# RdriveC1.net
KiCad netlist of a schematic drawn in Altium Designer
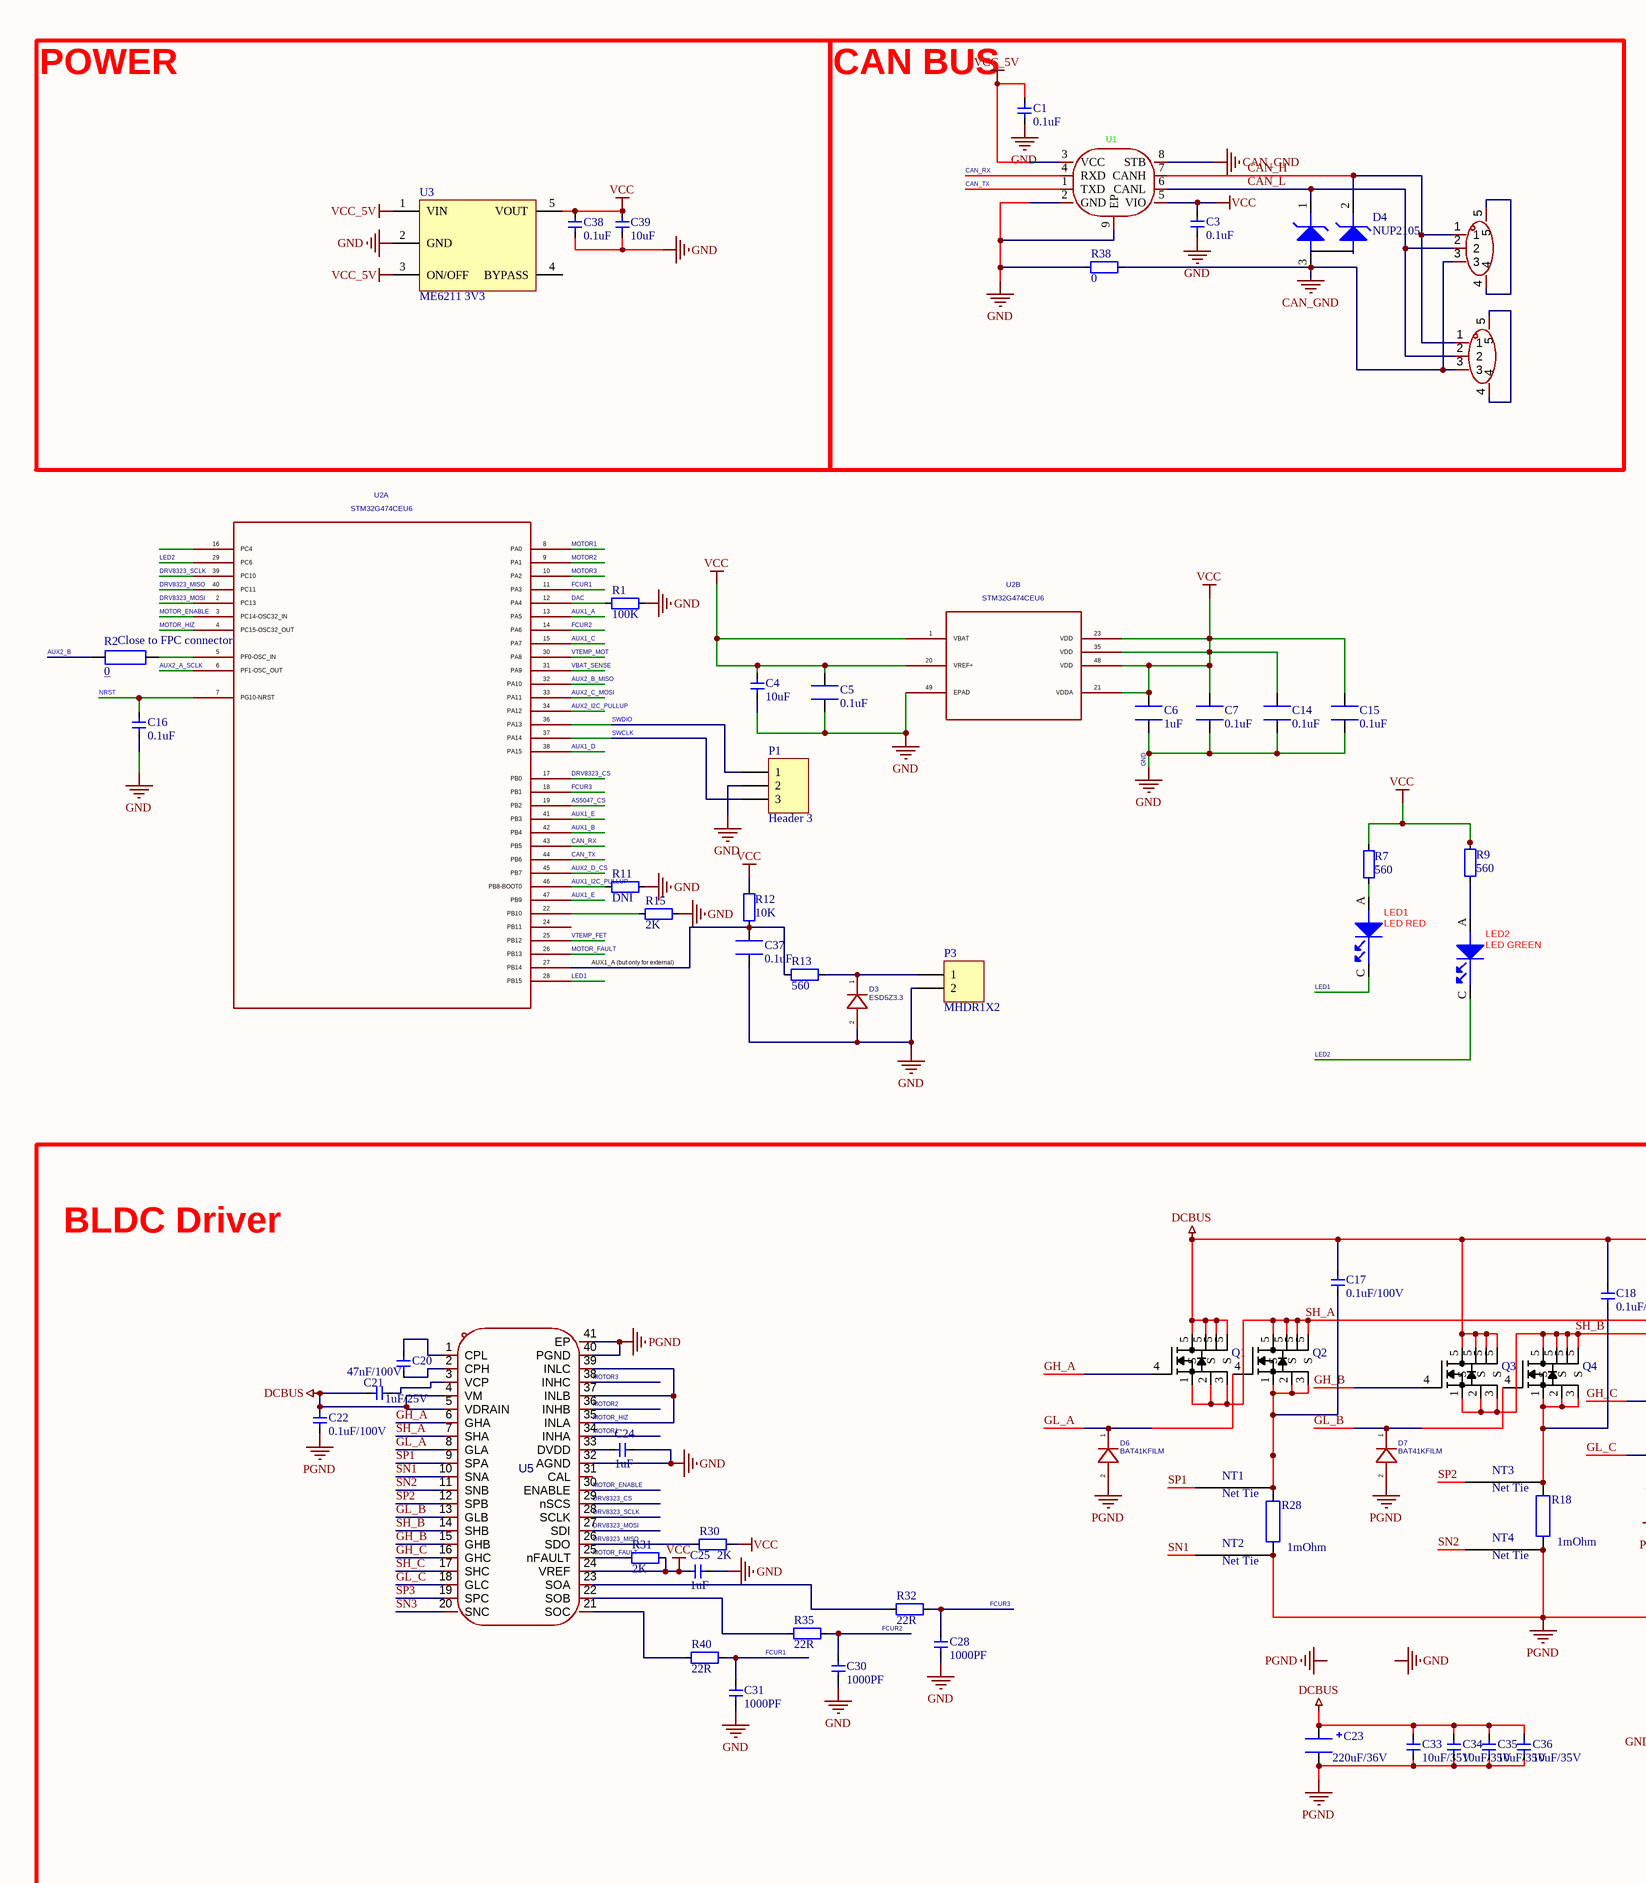
[diagram p0: RdriveC1.SchDoc, left]
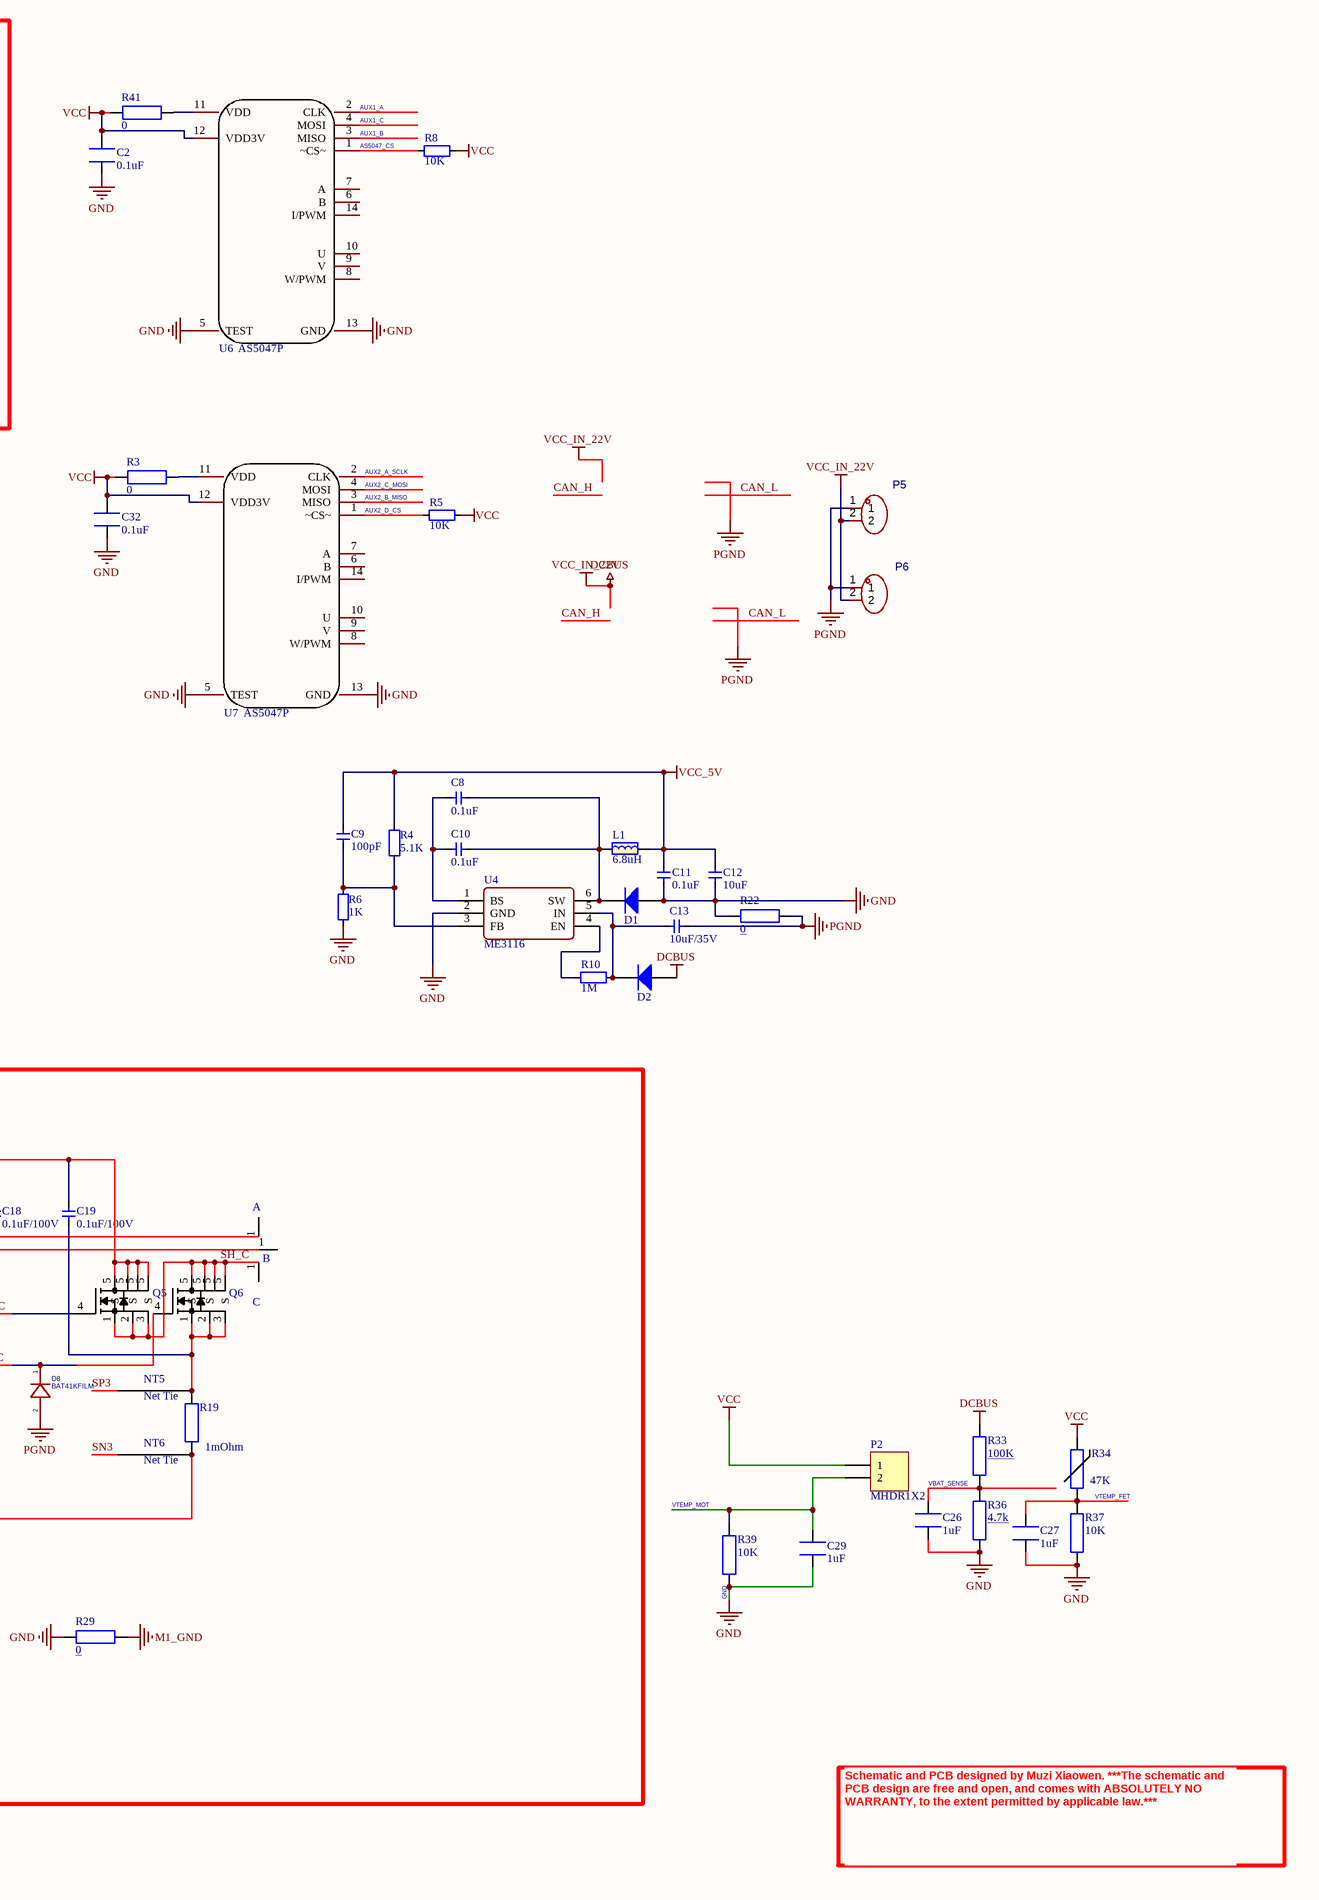
[diagram p1: RdriveC1.SchDoc, right]

(export (version "E")
  (design (tool "Eeschema 10.0.6"))
  (components
    (comp (ref "A") (value "M") (footprint "motor") (libsource (lib "RdriveS1") (part "M")))
    (comp (ref "B") (value "M") (footprint "motor") (libsource (lib "RdriveS1") (part "M")))
    (comp (ref "C") (value "M") (footprint "motor") (libsource (lib "RdriveS1") (part "M")))
    (comp (ref "C1")
      (value "0.1uF")
      (footprint "CAP_0402")
      (description "Capacitor")
      (libsource (lib "MyPcbLib") (part "电容-0402"))
    )
    (comp (ref "C2")
      (value "0.1uF")
      (footprint "CAP_0402")
      (description "CAP CER 0.1UF 50V X7R 0603")
      (fields
        (field (name "MANUFACTURER") "Murata Electronics North America")
        (field (name "MANUFACTURER PART NUMBER") "GRM188R71H104KA93D")
      )
      (libsource (lib "CustomComponents") (part "GRM188R71H104KA93D"))
    )
    (comp (ref "C3")
      (value "0.1uF")
      (footprint "CAP_0402")
      (description "Capacitor")
      (libsource (lib "MyPcbLib") (part "电容-0402"))
    )
    (comp (ref "C4")
      (value "10uF")
      (footprint "CAP_0402")
      (description "Capacitor")
      (libsource (lib "MyPcbLib") (part "电容-0402"))
    )
    (comp (ref "C5")
      (value "0.1uF")
      (footprint "CAP_0402")
      (description "CAP CER 0.1UF 50V X7R 0603")
      (fields
        (field (name "MANUFACTURER") "Murata Electronics North America")
        (field (name "MANUFACTURER PART NUMBER") "GRM188R71H104KA93D")
      )
      (libsource (lib "CustomComponents") (part "GRM188R71H104KA93D"))
    )
    (comp (ref "C6")
      (value "1uF")
      (footprint "CAP_0402")
      (description "CAP CER 1UF 50V X7R 0603")
      (fields
        (field (name "MANUFACTURER") "Murata Electronics North America")
        (field (name "MANUFACTURER PART NUMBER") "GRM188R71H104KA93D")
      )
      (libsource (lib "CustomComponents") (part "GRM188R71H104KA93D"))
    )
    (comp (ref "C7")
      (value "0.1uF")
      (footprint "CAP_0402")
      (description "CAP CER 0.1UF 50V X7R 0603")
      (fields
        (field (name "MANUFACTURER") "Murata Electronics North America")
        (field (name "MANUFACTURER PART NUMBER") "GRM188R71H104KA93D")
      )
      (libsource (lib "CustomComponents") (part "GRM188R71H104KA93D"))
    )
    (comp (ref "C8")
      (value "0.1uF")
      (footprint "CAP_0402")
      (description "Capacitor")
      (libsource (lib "MyPcbLib") (part "电容-0402"))
    )
    (comp (ref "C9")
      (value "100pF")
      (footprint "CAP_0402")
      (description "Capacitor")
      (libsource (lib "MyPcbLib") (part "电容-0402"))
    )
    (comp (ref "C10")
      (value "0.1uF")
      (footprint "CAP_0402")
      (description "Capacitor")
      (libsource (lib "MyPcbLib") (part "电容-0402"))
    )
    (comp (ref "C11")
      (value "0.1uF")
      (footprint "CAP_0402")
      (description "Capacitor")
      (libsource (lib "MyPcbLib") (part "电容-0402"))
    )
    (comp (ref "C12")
      (value "10uF")
      (footprint "CAP_0402")
      (description "Capacitor")
      (libsource (lib "MyPcbLib") (part "电容-0402"))
    )
    (comp (ref "C13")
      (value "10uF/35V")
      (footprint "C0603")
      (description "Capacitor")
      (libsource (lib "MyPcbLib") (part "电容-0402"))
    )
    (comp (ref "C14")
      (value "0.1uF")
      (footprint "CAP_0402")
      (description "CAP CER 0.1UF 50V X7R 0603")
      (fields
        (field (name "MANUFACTURER") "Murata Electronics North America")
        (field (name "MANUFACTURER PART NUMBER") "GRM188R71H104KA93D")
      )
      (libsource (lib "CustomComponents") (part "GRM188R71H104KA93D"))
    )
    (comp (ref "C15")
      (value "0.1uF")
      (footprint "CAP_0402")
      (description "CAP CER 0.1UF 50V X7R 0603")
      (fields
        (field (name "MANUFACTURER") "Murata Electronics North America")
        (field (name "MANUFACTURER PART NUMBER") "GRM188R71H104KA93D")
      )
      (libsource (lib "CustomComponents") (part "GRM188R71H104KA93D"))
    )
    (comp (ref "C16")
      (value "0.1uF")
      (footprint "CAP_0402")
      (description "Capacitor")
      (libsource (lib "MyPcbLib") (part "电容-0402"))
    )
    (comp (ref "C17")
      (value "0.1uF/100V")
      (footprint "1206-RES")
      (description "Capacitor")
      (libsource (lib "MyPcbLib") (part "电容-0402"))
    )
    (comp (ref "C18")
      (value "0.1uF/100V")
      (footprint "1206-RES")
      (description "Capacitor")
      (libsource (lib "MyPcbLib") (part "电容-0402"))
    )
    (comp (ref "C19")
      (value "0.1uF/100V")
      (footprint "1206-RES")
      (description "Capacitor")
      (libsource (lib "MyPcbLib") (part "电容-0402"))
    )
    (comp (ref "C20")
      (value "47nF/100V")
      (footprint "C0603")
      (description "Capacitor")
      (libsource (lib "MyPcbLib") (part "电容-0402"))
    )
    (comp (ref "C21")
      (value "1uF/25V")
      (footprint "C0603")
      (description "Capacitor")
      (libsource (lib "MyPcbLib") (part "电容-0402"))
    )
    (comp (ref "C22")
      (value "0.1uF/100V")
      (footprint "C0603")
      (description "Capacitor")
      (libsource (lib "MyPcbLib") (part "电容-0402"))
    )
    (comp (ref "C23")
      (value "220uF/36V")
      (footprint "3d-CAP-SMD_BD6.3-L6.6-W6.6-LS7.2-FD")
      (description "CAP, FP Series, 470 µF, 25 V, Radial Can - SMD, 10 mm")
      (fields
        (field (name "MANUFACTURER") "Panasonic Electronic Components")
        (field (name "TOLERANCE") "±20%")
      )
      (libsource (lib "CustomComponents") (part "EEEFP1E471AP"))
    )
    (comp (ref "C24")
      (value "1uF")
      (footprint "CAP_0402")
      (description "Capacitor")
      (libsource (lib "MyPcbLib") (part "电容-0402"))
    )
    (comp (ref "C25")
      (value "1uF")
      (footprint "CAP_0402")
      (description "Capacitor")
      (libsource (lib "MyPcbLib") (part "电容-0402"))
    )
    (comp (ref "C26")
      (value "1uF")
      (footprint "CAP_0402")
      (description "CAP CER 1UF 50V X7R 0603")
      (fields
        (field (name "MANUFACTURER") "Murata Electronics North America")
        (field (name "MANUFACTURER PART NUMBER") "GRM188R71H104KA93D")
      )
      (libsource (lib "CustomComponents") (part "GRM188R71H104KA93D"))
    )
    (comp (ref "C27")
      (value "1uF")
      (footprint "CAP_0402")
      (description "CAP CER 1UF 50V X7R 0603")
      (fields
        (field (name "MANUFACTURER") "Murata Electronics North America")
        (field (name "MANUFACTURER PART NUMBER") "GRM188R71H104KA93D")
      )
      (libsource (lib "CustomComponents") (part "GRM188R71H104KA93D"))
    )
    (comp (ref "C28")
      (value "1000PF")
      (footprint "CAP_0402")
      (description "Capacitor")
      (libsource (lib "MyPcbLib") (part "电容-0402"))
    )
    (comp (ref "C29")
      (value "1uF")
      (footprint "CAP_0402")
      (description "CAP CER 1UF 50V X7R 0603")
      (fields
        (field (name "MANUFACTURER") "Murata Electronics North America")
        (field (name "MANUFACTURER PART NUMBER") "GRM188R71H104KA93D")
      )
      (libsource (lib "CustomComponents") (part "GRM188R71H104KA93D"))
    )
    (comp (ref "C30")
      (value "1000PF")
      (footprint "CAP_0402")
      (description "Capacitor")
      (libsource (lib "MyPcbLib") (part "电容-0402"))
    )
    (comp (ref "C31")
      (value "1000PF")
      (footprint "CAP_0402")
      (description "Capacitor")
      (libsource (lib "MyPcbLib") (part "电容-0402"))
    )
    (comp (ref "C32")
      (value "0.1uF")
      (footprint "CAP_0402")
      (description "CAP CER 0.1UF 50V X7R 0603")
      (fields
        (field (name "MANUFACTURER") "Murata Electronics North America")
        (field (name "MANUFACTURER PART NUMBER") "GRM188R71H104KA93D")
      )
      (libsource (lib "CustomComponents") (part "GRM188R71H104KA93D"))
    )
    (comp (ref "C33")
      (value "10uF/35V")
      (footprint "C0603-3d")
      (description "Capacitor")
      (libsource (lib "MyPcbLib") (part "电容-0402"))
    )
    (comp (ref "C34")
      (value "10uF/35V")
      (footprint "C0603-3d")
      (description "Capacitor")
      (libsource (lib "MyPcbLib") (part "电容-0402"))
    )
    (comp (ref "C35")
      (value "10uF/35V")
      (footprint "C0603-3d")
      (description "Capacitor")
      (libsource (lib "MyPcbLib") (part "电容-0402"))
    )
    (comp (ref "C36")
      (value "10uF/35V")
      (footprint "C0603-3d")
      (description "Capacitor")
      (libsource (lib "MyPcbLib") (part "电容-0402"))
    )
    (comp (ref "C37")
      (value "0.1uF")
      (footprint "CAP_0402")
      (description "CAP CER 0.1UF 50V X7R 0603")
      (fields
        (field (name "MANUFACTURER") "Murata Electronics North America")
        (field (name "MANUFACTURER PART NUMBER") "GRM188R71H104KA93D")
      )
      (libsource (lib "CustomComponents") (part "GRM188R71H104KA93D"))
    )
    (comp (ref "C38")
      (value "0.1uF")
      (footprint "CAP_0402")
      (description "Capacitor")
      (libsource (lib "MyPcbLib") (part "电容-0402"))
    )
    (comp (ref "C39")
      (value "10uF")
      (footprint "CAP_0402")
      (description "Capacitor")
      (libsource (lib "MyPcbLib") (part "电容-0402"))
    )
    (comp (ref "CN1")
      (value "WAFER-GH1.25-3PLT-W1-P")
      (footprint "CONN-SMD_WAFER-GH1.25-3PLT-W1-P")
      (libsource (lib "altium-import") (part "root_0_WAFER-GH1.25-3PLT-W1-P_"))
    )
    (comp (ref "CN2")
      (value "WAFER-GH1.25-3PLT-W1-P")
      (footprint "CONN-SMD_WAFER-GH1.25-3PLT-W1-P")
      (libsource (lib "altium-import") (part "root_0_WAFER-GH1.25-3PLT-W1-P_"))
    )
    (comp (ref "D1")
      (value "二极管-5819W")
      (footprint "SOD-323")
      (description "40V")
      (libsource (lib "MyPcbLib") (part "二极管-5819W"))
    )
    (comp (ref "D2")
      (value "二极管-5819W")
      (footprint "SOD-323")
      (description "40V")
      (libsource (lib "MyPcbLib") (part "二极管-5819W"))
    )
    (comp (ref "D3")
      (value "ESD5Z3.3")
      (footprint "moteus:SOD-523_STM")
      (fields
        (field (name "MPN") "BAT41KFILM")
        (field (name "MF") "ST")
        (field (name "Comment") "moteus_BAT41KFILM")
      )
      (libsource (lib "altium-import") (part "root_1_moteus_BAT41KFILM_"))
    )
    (comp (ref "D4") (value "NUP2105") (footprint "SOT23-3") (libsource (lib "Schlib1") (part "NUP2105")))
    (comp (ref "D6")
      (value "BAT41KFILM")
      (footprint "moteus:SOD-523_STM")
      (fields (field (name "MF") "ST") (field (name "Comment") "moteus_BAT41KFILM"))
      (libsource (lib "altium-import") (part "root_1_moteus_BAT41KFILM_"))
    )
    (comp (ref "D7")
      (value "BAT41KFILM")
      (footprint "moteus:SOD-523_STM")
      (fields (field (name "MF") "ST") (field (name "Comment") "moteus_BAT41KFILM"))
      (libsource (lib "altium-import") (part "root_1_moteus_BAT41KFILM_"))
    )
    (comp (ref "D8")
      (value "BAT41KFILM")
      (footprint "moteus:SOD-523_STM")
      (fields (field (name "MF") "ST") (field (name "Comment") "moteus_BAT41KFILM"))
      (libsource (lib "altium-import") (part "root_1_moteus_BAT41KFILM_"))
    )
    (comp (ref "L1") (value "6.8uH") (footprint "IND-201612") (libsource (lib "MyPcbLib") (part "电感-201612")))
    (comp (ref "LED1")
      (value "LED RED")
      (description "LED GRN SGL RA 25mA 4.1V SMD")
      (libsource (lib "*") (part "LED"))
    )
    (comp (ref "LED2")
      (value "LED GREEN")
      (description "LED GRN SGL RA 25mA 4.1V SMD")
      (libsource (lib "*") (part "LED"))
    )
    (comp (ref "NT1")
      (value "0.25mm")
      (footprint "NetTie_0.25mm")
      (libsource (lib "CustomComponents") (part "NetTie_0.25mm"))
    )
    (comp (ref "NT2")
      (value "0.25mm")
      (footprint "NetTie_0.25mm")
      (libsource (lib "CustomComponents") (part "NetTie_0.25mm"))
    )
    (comp (ref "NT3")
      (value "0.25mm")
      (footprint "NetTie_0.25mm")
      (libsource (lib "CustomComponents") (part "NetTie_0.25mm"))
    )
    (comp (ref "NT4")
      (value "0.25mm")
      (footprint "NetTie_0.25mm")
      (libsource (lib "CustomComponents") (part "NetTie_0.25mm"))
    )
    (comp (ref "NT5")
      (value "0.25mm")
      (footprint "NetTie_0.25mm")
      (libsource (lib "CustomComponents") (part "NetTie_0.25mm"))
    )
    (comp (ref "NT6")
      (value "0.25mm")
      (footprint "NetTie_0.25mm")
      (libsource (lib "CustomComponents") (part "NetTie_0.25mm"))
    )
    (comp (ref "P1")
      (value "Header 3")
      (footprint "HDR1X3")
      (description "Header, 3-Pin")
      (fields (field (name "PUBLISHER") "Altium Limited"))
      (libsource (lib "Miscellaneous Connectors") (part "Header 3"))
    )
    (comp (ref "P2")
      (value "MHDR1X2")
      (footprint "MHDR1X2")
      (description "Header, 2-Pin")
      (fields (field (name "PUBLISHER") "Altium Limited"))
      (libsource (lib "Miscellaneous Connectors") (part "MHDR1X2"))
    )
    (comp (ref "P3")
      (value "MHDR1X2")
      (footprint "CONN-TH_2P-P1.50_HCTL_HC-ZH1.5-2AW")
      (description "Header, 2-Pin")
      (fields (field (name "PUBLISHER") "Altium Limited"))
      (libsource (lib "Miscellaneous Connectors") (part "MHDR1X2"))
    )
    (comp (ref "P5")
      (value "HC-MX3.0-2*1AW")
      (footprint "CONN-TH_XT30UW-F.G.Y")
      (libsource (lib "altium-import") (part "root_0_HC-MX3.0-2*1AW_"))
    )
    (comp (ref "P6")
      (value "HC-MX3.0-2*1AW")
      (footprint "CONN-TH_XT30UW-F.G.Y")
      (libsource (lib "altium-import") (part "root_0_HC-MX3.0-2*1AW_"))
    )
    (comp (ref "Q1")
      (value "SE3082G2")
      (footprint "DFN-8_L5.9-W5.2-P1.27-LS6.2-BL")
      (description "MOSFET N-CH 30V 13A SO8FL")
      (fields
        (field (name "MANUFACTURER") "ON Semiconductor")
        (field (name "MANUFACTURER PART NUMBER") "NTMFS4935NT1G")
      )
      (libsource (lib "odrivelib") (part "SE3082G2"))
    )
    (comp (ref "Q2")
      (value "SE3082G2")
      (footprint "DFN-8_L5.9-W5.2-P1.27-LS6.2-BL")
      (description "MOSFET N-CH 30V 13A SO8FL")
      (fields
        (field (name "MANUFACTURER") "ON Semiconductor")
        (field (name "MANUFACTURER PART NUMBER") "NTMFS4935NT1G")
      )
      (libsource (lib "odrivelib") (part "SE3082G2"))
    )
    (comp (ref "Q3")
      (value "SE3082G2")
      (footprint "DFN-8_L5.9-W5.2-P1.27-LS6.2-BL")
      (description "MOSFET N-CH 30V 13A SO8FL")
      (fields
        (field (name "MANUFACTURER") "ON Semiconductor")
        (field (name "MANUFACTURER PART NUMBER") "NTMFS4935NT1G")
      )
      (libsource (lib "odrivelib") (part "SE3082G2"))
    )
    (comp (ref "Q4")
      (value "SE3082G2")
      (footprint "DFN-8_L5.9-W5.2-P1.27-LS6.2-BL")
      (description "MOSFET N-CH 30V 13A SO8FL")
      (fields
        (field (name "MANUFACTURER") "ON Semiconductor")
        (field (name "MANUFACTURER PART NUMBER") "NTMFS4935NT1G")
      )
      (libsource (lib "odrivelib") (part "SE3082G2"))
    )
    (comp (ref "Q5")
      (value "SE3082G2")
      (footprint "DFN-8_L5.9-W5.2-P1.27-LS6.2-BL")
      (description "MOSFET N-CH 30V 13A SO8FL")
      (fields
        (field (name "MANUFACTURER") "ON Semiconductor")
        (field (name "MANUFACTURER PART NUMBER") "NTMFS4935NT1G")
      )
      (libsource (lib "odrivelib") (part "SE3082G2"))
    )
    (comp (ref "Q6")
      (value "SE3082G2")
      (footprint "DFN-8_L5.9-W5.2-P1.27-LS6.2-BL")
      (description "MOSFET N-CH 30V 13A SO8FL")
      (fields
        (field (name "MANUFACTURER") "ON Semiconductor")
        (field (name "MANUFACTURER PART NUMBER") "NTMFS4935NT1G")
      )
      (libsource (lib "odrivelib") (part "SE3082G2"))
    )
    (comp (ref "R1")
      (value "100K")
      (footprint "RES_0402")
      (description "Resistor")
      (libsource (lib "MyPcbLib") (part "电阻-0402"))
    )
    (comp (ref "R2")
      (value "0")
      (footprint "RES_0402")
      (description "RES SMD 1K OHM 1% 1/10W 0603")
      (fields (field (name "MANUFACTURER") "Yageo") (field (name "TOLERANCE") "±1%"))
      (libsource (lib "CustomComponents") (part "RC0603FR-071KL"))
    )
    (comp (ref "R3")
      (value "0")
      (footprint "RES_0402")
      (description "RES SMD 1K OHM 1% 1/10W 0603")
      (fields (field (name "MANUFACTURER") "Yageo") (field (name "TOLERANCE") "±1%"))
      (libsource (lib "CustomComponents") (part "RC0603FR-071KL"))
    )
    (comp (ref "R4")
      (value "5.1K")
      (footprint "RES_0402")
      (description "Resistor")
      (libsource (lib "") (part "电阻-0402_1"))
    )
    (comp (ref "R5")
      (value "10K")
      (footprint "RES_0402")
      (description "Resistor")
      (libsource (lib "") (part "电阻-0402_2"))
    )
    (comp (ref "R6")
      (value "1K")
      (footprint "RES_0402")
      (description "Resistor")
      (libsource (lib "") (part "电阻-0402_1"))
    )
    (comp (ref "R7")
      (value "560")
      (footprint "RES_0402")
      (description "Resistor")
      (libsource (lib "") (part "电阻-0402_1"))
    )
    (comp (ref "R8")
      (value "10K")
      (footprint "RES_0402")
      (description "Resistor")
      (libsource (lib "") (part "电阻-0402_2"))
    )
    (comp (ref "R9")
      (value "560")
      (footprint "RES_0402")
      (description "Resistor")
      (libsource (lib "") (part "电阻-0402_1"))
    )
    (comp (ref "R10")
      (value "1M")
      (footprint "RES_0402")
      (description "Resistor")
      (libsource (lib "MyPcbLib") (part "电阻-0402"))
    )
    (comp (ref "R11")
      (value "DNI")
      (footprint "RES_0402")
      (description "Resistor")
      (libsource (lib "MyPcbLib") (part "电阻-0402"))
    )
    (comp (ref "R12")
      (value "10K")
      (footprint "RES_0402")
      (description "Resistor")
      (libsource (lib "") (part "电阻-0402_1"))
    )
    (comp (ref "R13")
      (value "560")
      (footprint "RES_0402")
      (description "Resistor")
      (libsource (lib "MyPcbLib") (part "电阻-0402"))
    )
    (comp (ref "R15")
      (value "2K")
      (footprint "RES_0402")
      (description "Resistor")
      (libsource (lib "MyPcbLib") (part "电阻-0402"))
    )
    (comp (ref "R18")
      (value "1mOhm")
      (footprint "1206-RES")
      (description "RES SMD 0.0005 OHM 1% 3W 2512")
      (fields (field (name "MANUFACTURER") "Riedon") (field (name "TOLERANCE") "±1%"))
      (libsource (lib "CustomComponents") (part "CSR2512C0R0005F"))
    )
    (comp (ref "R19")
      (value "1mOhm")
      (footprint "1206-RES")
      (description "RES SMD 0.0005 OHM 1% 3W 2512")
      (fields (field (name "MANUFACTURER") "Riedon") (field (name "TOLERANCE") "±1%"))
      (libsource (lib "CustomComponents") (part "CSR2512C0R0005F"))
    )
    (comp (ref "R22")
      (value "0")
      (footprint "1206-RES")
      (description "RES SMD 1K OHM 1% 1/10W 0603")
      (fields (field (name "MANUFACTURER") "Yageo") (field (name "TOLERANCE") "±1%"))
      (libsource (lib "CustomComponents") (part "RC0603FR-071KL"))
    )
    (comp (ref "R28")
      (value "1mOhm")
      (footprint "1206-RES")
      (description "RES SMD 0.0005 OHM 1% 3W 2512")
      (fields (field (name "MANUFACTURER") "Riedon") (field (name "TOLERANCE") "±1%"))
      (libsource (lib "CustomComponents") (part "CSR2512C0R0005F"))
    )
    (comp (ref "R29")
      (value "0")
      (footprint "RES_0402")
      (description "RES SMD 1K OHM 1% 1/10W 0603")
      (fields (field (name "MANUFACTURER") "Yageo") (field (name "TOLERANCE") "±1%"))
      (libsource (lib "CustomComponents") (part "RC0603FR-071KL"))
    )
    (comp (ref "R30")
      (value "2K")
      (footprint "RES_0402")
      (description "Resistor")
      (libsource (lib "MyPcbLib") (part "电阻-0402"))
    )
    (comp (ref "R31")
      (value "2K")
      (footprint "RES_0402")
      (description "Resistor")
      (libsource (lib "MyPcbLib") (part "电阻-0402"))
    )
    (comp (ref "R32")
      (value "22R")
      (footprint "RES_0402")
      (description "Resistor")
      (libsource (lib "") (part "电阻-0402_2"))
    )
    (comp (ref "R33")
      (value "100K")
      (footprint "RES_0402")
      (description "RES SMD 1K OHM 1% 1/10W 0603")
      (fields (field (name "MANUFACTURER") "Yageo") (field (name "TOLERANCE") "±1%"))
      (libsource (lib "CustomComponents") (part "RC0603FR-071KL"))
    )
    (comp (ref "R34")
      (value "47K")
      (footprint "CAP_0402")
      (description "THERMISTOR 10K OHM NTC 0402 SMD")
      (libsource (lib "CustomComponents") (part "NCP15XH103F03RC"))
    )
    (comp (ref "R35")
      (value "22R")
      (footprint "RES_0402")
      (description "Resistor")
      (libsource (lib "") (part "电阻-0402_2"))
    )
    (comp (ref "R36")
      (value "4.7k")
      (footprint "RES_0402")
      (description "RES SMD 1K OHM 1% 1/10W 0603")
      (fields (field (name "MANUFACTURER") "Yageo") (field (name "TOLERANCE") "±1%"))
      (libsource (lib "CustomComponents") (part "RC0603FR-071KL"))
    )
    (comp (ref "R37")
      (value "10K")
      (footprint "RES_0402")
      (description "RES SMD 3.3K OHM 1% 1/10W 0603")
      (fields
        (field (name "MANUFACTURER") "Yageo")
        (field (name "MANUFACTURER PART NUMBER") "RC0603FR-073K3L")
      )
      (libsource (lib "CustomComponents") (part "RC0603FR-073K3L"))
    )
    (comp (ref "R38")
      (value "0")
      (footprint "RES_0402")
      (description "Resistor")
      (libsource (lib "MyPcbLib") (part "电阻-0402"))
    )
    (comp (ref "R39")
      (value "10K")
      (footprint "RES_0402")
      (description "RES SMD 3.3K OHM 1% 1/10W 0603")
      (fields
        (field (name "MANUFACTURER") "Yageo")
        (field (name "MANUFACTURER PART NUMBER") "RC0603FR-073K3L")
      )
      (libsource (lib "CustomComponents") (part "RC0603FR-073K3L"))
    )
    (comp (ref "R40")
      (value "22R")
      (footprint "RES_0402")
      (description "Resistor")
      (libsource (lib "") (part "电阻-0402_2"))
    )
    (comp (ref "R41")
      (value "0")
      (footprint "RES_0402")
      (description "RES SMD 1K OHM 1% 1/10W 0603")
      (fields (field (name "MANUFACTURER") "Yageo") (field (name "TOLERANCE") "±1%"))
      (libsource (lib "CustomComponents") (part "RC0603FR-071KL"))
    )
    (comp (ref "U1")
      (value "TCAN1057AVDRBRQ1")
      (footprint "SOIC8_2")
      (fields (field (name "MANUFACTURER") "SIT(芯力特)") (field (name "MANUFACTURER PART") "SIT1042ATK/3"))
      (libsource (lib "altium-import") (part "root_0_SIT1042ATK/3_"))
    )
    (comp (ref "U2")
      (value "STM32G474CEU6")
      (footprint "moteus:UFQFPN-48_7X7X0P55MM")
      (fields (field (name "MF") "ST") (field (name "Comment") "moteus_STM32G474CEU6"))
      (libsource (lib "altium-import") (part "root_0_mirrored_moteus_STM32G474CEU6_"))
    )
    (comp (ref "U3")
      (value "ME6211 3V3")
      (footprint "SOT23-5-3d")
      (description "LDO")
      (libsource (lib "MyPcbLib") (part "LP2992"))
    )
    (comp (ref "U4")
      (value "ME3116")
      (footprint "SOT23-6")
      (description "DC-DC")
      (libsource (lib "MyPcbLib") (part "ME3116"))
    )
    (comp (ref "U5")
      (value "DRV8323SRTAR")
      (footprint "WQFN-40_L6.0-W6.0-P0.50-TL-EP4.5")
      (libsource (lib "altium-import") (part "root_0_DRV8323SRTAR_"))
    )
    (comp (ref "U6")
      (value "AS5047P")
      (footprint "TSSOP14_2")
      (fields (field (name "DEVICE") "AS5047P"))
      (libsource (lib "altium-import") (part "root_0_AS5047P_"))
    )
    (comp (ref "U7")
      (value "AS5047P")
      (footprint "TSSOP14_2")
      (fields (field (name "DEVICE") "AS5047P"))
      (libsource (lib "altium-import") (part "root_0_AS5047P_"))
    )
  )
  (nets
    (net (code "1") (name "/AS5047_CS") (class "Default")
      (node (ref "R8") (pin "2") (pinfunction "2_2") (pintype "passive"))
      (node (ref "U2") (pin "19") (pinfunction "PB2_19") (pintype "passive"))
      (node (ref "U6") (pin "1") (pinfunction "~CS~_1") (pintype "passive"))
    )
    (net (code "2") (name "/AUX1_A") (class "Default")
      (node (ref "U2") (pin "13") (pinfunction "PA5_13") (pintype "passive"))
      (node (ref "U6") (pin "2") (pinfunction "CLK_2") (pintype "passive"))
    )
    (net (code "3") (name "/AUX1_B") (class "Default")
      (node (ref "U2") (pin "42") (pinfunction "PB4_42") (pintype "passive"))
      (node (ref "U6") (pin "3") (pinfunction "MISO_3") (pintype "passive"))
    )
    (net (code "4") (name "/AUX1_C") (class "Default")
      (node (ref "U2") (pin "15") (pinfunction "PA7_15") (pintype "passive"))
      (node (ref "U6") (pin "4") (pinfunction "MOSI_4") (pintype "passive"))
    )
    (net (code "5") (name "/AUX1_D") (class "Default")
      (node (ref "U2") (pin "38") (pinfunction "PA15_38") (pintype "passive"))
    )
    (net (code "6") (name "/AUX1_E") (class "Default")
      (node (ref "U2") (pin "41") (pinfunction "PB3_41") (pintype "passive"))
      (node (ref "U2") (pin "47") (pinfunction "PB9_47") (pintype "passive"))
    )
    (net (code "7") (name "/AUX1_I2C_PULLUP") (class "Default")
      (node (ref "R11") (pin "1") (pinfunction "1_1") (pintype "passive"))
      (node (ref "U2") (pin "46") (pinfunction "PB8-BOOT0_46") (pintype "passive"))
    )
    (net (code "8") (name "/AUX2_A_SCLK") (class "Default")
      (node (ref "U2") (pin "6") (pinfunction "PF1-OSC_OUT_6") (pintype "passive"))
      (node (ref "U7") (pin "2") (pinfunction "CLK_2") (pintype "passive"))
    )
    (net (code "9") (name "/AUX2_B") (class "Default")
      (node (ref "R2") (pin "1") (pinfunction "0_1") (pintype "passive"))
    )
    (net (code "10") (name "/AUX2_B_MISO") (class "Default")
      (node (ref "U2") (pin "32") (pinfunction "PA10_32") (pintype "passive"))
      (node (ref "U7") (pin "3") (pinfunction "MISO_3") (pintype "passive"))
    )
    (net (code "11") (name "/AUX2_C_MOSI") (class "Default")
      (node (ref "U2") (pin "33") (pinfunction "PA11_33") (pintype "passive"))
      (node (ref "U7") (pin "4") (pinfunction "MOSI_4") (pintype "passive"))
    )
    (net (code "12") (name "/AUX2_D_CS") (class "Default")
      (node (ref "R5") (pin "2") (pinfunction "2_2") (pintype "passive"))
      (node (ref "U2") (pin "45") (pinfunction "PB7_45") (pintype "passive"))
      (node (ref "U7") (pin "1") (pinfunction "~CS~_1") (pintype "passive"))
    )
    (net (code "13") (name "/AUX2_I2C_PULLUP") (class "Default")
      (node (ref "U2") (pin "34") (pinfunction "PA12_34") (pintype "passive"))
    )
    (net (code "14") (name "/CAN_H") (class "Default")
      (node (ref "CN1") (pin "1") (pinfunction "1_1") (pintype "passive"))
      (node (ref "CN2") (pin "1") (pinfunction "1_1") (pintype "passive"))
      (node (ref "D4") (pin "2") (pinfunction "C_2") (pintype "passive"))
      (node (ref "U1") (pin "7") (pinfunction "CANH_7") (pintype "passive"))
    )
    (net (code "15") (name "/CAN_L") (class "Default")
      (node (ref "CN1") (pin "2") (pinfunction "2_2") (pintype "passive"))
      (node (ref "CN2") (pin "2") (pinfunction "2_2") (pintype "passive"))
      (node (ref "D4") (pin "1") (pinfunction "C_1") (pintype "passive"))
      (node (ref "U1") (pin "6") (pinfunction "CANL_6") (pintype "passive"))
    )
    (net (code "16") (name "/CAN_RX") (class "Default")
      (node (ref "U1") (pin "4") (pinfunction "RXD_4") (pintype "passive"))
      (node (ref "U2") (pin "43") (pinfunction "PB5_43") (pintype "passive"))
    )
    (net (code "17") (name "/CAN_TX") (class "Default")
      (node (ref "U1") (pin "1") (pinfunction "TXD_1") (pintype "passive"))
      (node (ref "U2") (pin "44") (pinfunction "PB6_44") (pintype "passive"))
    )
    (net (code "18") (name "/DAC") (class "Default")
      (node (ref "R1") (pin "1") (pinfunction "1_1") (pintype "passive"))
      (node (ref "U2") (pin "12") (pinfunction "PA4_12") (pintype "passive"))
    )
    (net (code "19") (name "/DRV8323_CS") (class "Default")
      (node (ref "U2") (pin "17") (pinfunction "PB0_17") (pintype "passive"))
      (node (ref "U5") (pin "29") (pinfunction "nSCS_29") (pintype "passive"))
    )
    (net (code "20") (name "/DRV8323_MISO") (class "Default")
      (node (ref "R30") (pin "1") (pinfunction "1_1") (pintype "passive"))
      (node (ref "U2") (pin "40") (pinfunction "PC11_40") (pintype "passive"))
      (node (ref "U5") (pin "26") (pinfunction "SDO_26") (pintype "passive"))
    )
    (net (code "21") (name "/DRV8323_MOSI") (class "Default")
      (node (ref "U2") (pin "2") (pinfunction "PC13_2") (pintype "passive"))
      (node (ref "U5") (pin "27") (pinfunction "SDI_27") (pintype "passive"))
    )
    (net (code "22") (name "/DRV8323_SCLK") (class "Default")
      (node (ref "U2") (pin "39") (pinfunction "PC10_39") (pintype "passive"))
      (node (ref "U5") (pin "28") (pinfunction "SCLK_28") (pintype "passive"))
    )
    (net (code "23") (name "/FCUR1") (class "Default")
      (node (ref "C31") (pin "2") (pinfunction "2_2") (pintype "passive"))
      (node (ref "R40") (pin "1") (pinfunction "1_1") (pintype "passive"))
      (node (ref "U2") (pin "11") (pinfunction "PA3_11") (pintype "passive"))
    )
    (net (code "24") (name "/FCUR2") (class "Default")
      (node (ref "C30") (pin "2") (pinfunction "2_2") (pintype "passive"))
      (node (ref "R35") (pin "1") (pinfunction "1_1") (pintype "passive"))
      (node (ref "U2") (pin "14") (pinfunction "PA6_14") (pintype "passive"))
    )
    (net (code "25") (name "/FCUR3") (class "Default")
      (node (ref "C28") (pin "2") (pinfunction "2_2") (pintype "passive"))
      (node (ref "R32") (pin "1") (pinfunction "1_1") (pintype "passive"))
      (node (ref "U2") (pin "18") (pinfunction "PB1_18") (pintype "passive"))
    )
    (net (code "26") (name "/GH_A") (class "Default")
      (node (ref "Q1") (pin "4") (pinfunction "G1_4") (pintype "passive"))
      (node (ref "U5") (pin "6") (pinfunction "GHA_6") (pintype "passive"))
    )
    (net (code "27") (name "/GH_B") (class "Default")
      (node (ref "Q3") (pin "4") (pinfunction "G1_4") (pintype "passive"))
      (node (ref "U5") (pin "15") (pinfunction "GHB_15") (pintype "passive"))
    )
    (net (code "28") (name "/GH_C") (class "Default")
      (node (ref "Q5") (pin "4") (pinfunction "G1_4") (pintype "passive"))
      (node (ref "U5") (pin "16") (pinfunction "GHC_16") (pintype "passive"))
    )
    (net (code "29") (name "/GL_A") (class "Default")
      (node (ref "D6") (pin "1") (pintype "passive"))
      (node (ref "Q2") (pin "4") (pinfunction "G1_4") (pintype "passive"))
      (node (ref "U5") (pin "8") (pinfunction "GLA_8") (pintype "passive"))
    )
    (net (code "30") (name "/GL_B") (class "Default")
      (node (ref "D7") (pin "1") (pintype "passive"))
      (node (ref "Q4") (pin "4") (pinfunction "G1_4") (pintype "passive"))
      (node (ref "U5") (pin "13") (pinfunction "GLB_13") (pintype "passive"))
    )
    (net (code "31") (name "/GL_C") (class "Default")
      (node (ref "D8") (pin "1") (pintype "passive"))
      (node (ref "Q6") (pin "4") (pinfunction "G1_4") (pintype "passive"))
      (node (ref "U5") (pin "18") (pinfunction "GLC_18") (pintype "passive"))
    )
    (net (code "32") (name "/LED1") (class "Default")
      (node (ref "LED1") (pin "C") (pinfunction "CATHODE_C") (pintype "passive"))
      (node (ref "U2") (pin "28") (pinfunction "PB15_28") (pintype "passive"))
    )
    (net (code "33") (name "/LED2") (class "Default")
      (node (ref "LED2") (pin "C") (pinfunction "CATHODE_C") (pintype "passive"))
      (node (ref "U2") (pin "29") (pinfunction "PC6_29") (pintype "passive"))
    )
    (net (code "34") (name "/MOTOR1") (class "Default")
      (node (ref "U2") (pin "8") (pinfunction "PA0_8") (pintype "passive"))
      (node (ref "U5") (pin "34") (pinfunction "INHA_34") (pintype "passive"))
    )
    (net (code "35") (name "/MOTOR2") (class "Default")
      (node (ref "U2") (pin "9") (pinfunction "PA1_9") (pintype "passive"))
      (node (ref "U5") (pin "36") (pinfunction "INHB_36") (pintype "passive"))
    )
    (net (code "36") (name "/MOTOR3") (class "Default")
      (node (ref "U2") (pin "10") (pinfunction "PA2_10") (pintype "passive"))
      (node (ref "U5") (pin "38") (pinfunction "INHC_38") (pintype "passive"))
    )
    (net (code "37") (name "/MOTOR_ENABLE") (class "Default")
      (node (ref "U2") (pin "3") (pinfunction "PC14-OSC32_IN_3") (pintype "passive"))
      (node (ref "U5") (pin "30") (pinfunction "ENABLE_30") (pintype "passive"))
    )
    (net (code "38") (name "/MOTOR_FAULT") (class "Default")
      (node (ref "R31") (pin "1") (pinfunction "1_1") (pintype "passive"))
      (node (ref "U2") (pin "26") (pinfunction "PB13_26") (pintype "passive"))
      (node (ref "U5") (pin "25") (pinfunction "nFAULT_25") (pintype "passive"))
    )
    (net (code "39") (name "/MOTOR_HIZ") (class "Default")
      (node (ref "U2") (pin "4") (pinfunction "PC15-OSC32_OUT_4") (pintype "passive"))
      (node (ref "U5") (pin "35") (pinfunction "INLA_35") (pintype "passive"))
      (node (ref "U5") (pin "37") (pinfunction "INLB_37") (pintype "passive"))
      (node (ref "U5") (pin "39") (pinfunction "INLC_39") (pintype "passive"))
    )
    (net (code "40") (name "/NRST") (class "Default")
      (node (ref "C16") (pin "2") (pinfunction "2_2") (pintype "passive"))
      (node (ref "U2") (pin "7") (pinfunction "PG10-NRST_7") (pintype "passive"))
    )
    (net (code "41") (name "/SH_A") (class "Default")
      (node (ref "A") (pin "1") (pintype "passive"))
      (node (ref "Q1") (pin "1") (pinfunction "S_1") (pintype "passive"))
      (node (ref "Q1") (pin "2") (pinfunction "S_2") (pintype "passive"))
      (node (ref "Q1") (pin "3") (pinfunction "S_3") (pintype "passive"))
      (node (ref "Q2") (pin "5") (pinfunction "D_5") (pintype "passive"))
      (node (ref "U5") (pin "7") (pinfunction "SHA_7") (pintype "passive"))
    )
    (net (code "42") (name "/SH_B") (class "Default")
      (node (ref "B") (pin "1") (pintype "passive"))
      (node (ref "Q3") (pin "1") (pinfunction "S_1") (pintype "passive"))
      (node (ref "Q3") (pin "2") (pinfunction "S_2") (pintype "passive"))
      (node (ref "Q3") (pin "3") (pinfunction "S_3") (pintype "passive"))
      (node (ref "Q4") (pin "5") (pinfunction "D_5") (pintype "passive"))
      (node (ref "U5") (pin "14") (pinfunction "SHB_14") (pintype "passive"))
    )
    (net (code "43") (name "/SH_C") (class "Default")
      (node (ref "C") (pin "1") (pintype "passive"))
      (node (ref "Q5") (pin "1") (pinfunction "S_1") (pintype "passive"))
      (node (ref "Q5") (pin "2") (pinfunction "S_2") (pintype "passive"))
      (node (ref "Q5") (pin "3") (pinfunction "S_3") (pintype "passive"))
      (node (ref "Q6") (pin "5") (pinfunction "D_5") (pintype "passive"))
      (node (ref "U5") (pin "17") (pinfunction "SHC_17") (pintype "passive"))
    )
    (net (code "44") (name "/SN1") (class "Default")
      (node (ref "NT2") (pin "1") (pintype "passive"))
      (node (ref "U5") (pin "10") (pinfunction "SNA_10") (pintype "passive"))
    )
    (net (code "45") (name "/SN2") (class "Default")
      (node (ref "NT4") (pin "1") (pintype "passive"))
      (node (ref "U5") (pin "11") (pinfunction "SNB_11") (pintype "passive"))
    )
    (net (code "46") (name "/SN3") (class "Default")
      (node (ref "NT6") (pin "1") (pintype "passive"))
      (node (ref "U5") (pin "20") (pinfunction "SNC_20") (pintype "passive"))
    )
    (net (code "47") (name "/SP1") (class "Default")
      (node (ref "NT1") (pin "1") (pintype "passive"))
      (node (ref "U5") (pin "9") (pinfunction "SPA_9") (pintype "passive"))
    )
    (net (code "48") (name "/SP2") (class "Default")
      (node (ref "NT3") (pin "1") (pintype "passive"))
      (node (ref "U5") (pin "12") (pinfunction "SPB_12") (pintype "passive"))
    )
    (net (code "49") (name "/SP3") (class "Default")
      (node (ref "NT5") (pin "1") (pintype "passive"))
      (node (ref "U5") (pin "19") (pinfunction "SPC_19") (pintype "passive"))
    )
    (net (code "50") (name "/SWCLK") (class "Default")
      (node (ref "P1") (pin "3") (pinfunction "3_3") (pintype "passive"))
      (node (ref "U2") (pin "37") (pinfunction "PA14_37") (pintype "passive"))
    )
    (net (code "51") (name "/SWDIO") (class "Default")
      (node (ref "P1") (pin "1") (pinfunction "1_1") (pintype "passive"))
      (node (ref "U2") (pin "36") (pinfunction "PA13_36") (pintype "passive"))
    )
    (net (code "52") (name "/VBAT_SENSE") (class "Default")
      (node (ref "C26") (pin "1") (pinfunction "1_1") (pintype "passive"))
      (node (ref "R33") (pin "1") (pinfunction "0_1") (pintype "passive"))
      (node (ref "R36") (pin "2") (pinfunction "0_2") (pintype "passive"))
      (node (ref "U2") (pin "31") (pinfunction "PA9_31") (pintype "passive"))
    )
    (net (code "53") (name "/VTEMP_FET") (class "Default")
      (node (ref "C27") (pin "1") (pinfunction "1_1") (pintype "passive"))
      (node (ref "R34") (pin "1") (pinfunction "0_1") (pintype "passive"))
      (node (ref "R37") (pin "1") (pinfunction "0_1") (pintype "passive"))
      (node (ref "U2") (pin "25") (pinfunction "PB12_25") (pintype "passive"))
    )
    (net (code "54") (name "/VTEMP_MOT") (class "Default")
      (node (ref "C29") (pin "1") (pinfunction "1_1") (pintype "passive"))
      (node (ref "P2") (pin "2") (pinfunction "2_2") (pintype "passive"))
      (node (ref "R39") (pin "1") (pinfunction "0_1") (pintype "passive"))
      (node (ref "U2") (pin "30") (pinfunction "PA8_30") (pintype "passive"))
    )
    (net (code "55") (name "CAN_GND") (class "Default")
      (node (ref "CN1") (pin "3") (pinfunction "3_3") (pintype "passive"))
      (node (ref "CN2") (pin "3") (pinfunction "3_3") (pintype "passive"))
      (node (ref "D4") (pin "3") (pinfunction "A_3") (pintype "passive"))
      (node (ref "R38") (pin "2") (pinfunction "2_2") (pintype "passive"))
      (node (ref "U1") (pin "8") (pinfunction "STB_8") (pintype "passive"))
    )
    (net (code "56") (name "DCBUS") (class "Default")
      (node (ref "C17") (pin "1") (pinfunction "1_1") (pintype "passive"))
      (node (ref "C18") (pin "1") (pinfunction "1_1") (pintype "passive"))
      (node (ref "C19") (pin "1") (pinfunction "1_1") (pintype "passive"))
      (node (ref "C21") (pin "2") (pinfunction "2_2") (pintype "passive"))
      (node (ref "C22") (pin "1") (pinfunction "1_1") (pintype "passive"))
      (node (ref "C23") (pin "1") (pinfunction "1_1") (pintype "passive"))
      (node (ref "C33") (pin "2") (pinfunction "2_2") (pintype "passive"))
      (node (ref "C34") (pin "2") (pinfunction "2_2") (pintype "passive"))
      (node (ref "C35") (pin "2") (pinfunction "2_2") (pintype "passive"))
      (node (ref "C36") (pin "2") (pinfunction "2_2") (pintype "passive"))
      (node (ref "D2") (pin "1") (pinfunction "A_1") (pintype "passive"))
      (node (ref "P5") (pin "2") (pinfunction "2_2") (pintype "passive"))
      (node (ref "P6") (pin "2") (pinfunction "2_2") (pintype "passive"))
      (node (ref "Q1") (pin "5") (pinfunction "D_5") (pintype "passive"))
      (node (ref "Q3") (pin "5") (pinfunction "D_5") (pintype "passive"))
      (node (ref "Q5") (pin "5") (pinfunction "D_5") (pintype "passive"))
      (node (ref "R33") (pin "2") (pinfunction "0_2") (pintype "passive"))
      (node (ref "U5") (pin "4") (pinfunction "VM_4") (pintype "passive"))
      (node (ref "U5") (pin "5") (pinfunction "VDRAIN_5") (pintype "passive"))
    )
    (net (code "57") (name "GND") (class "Default")
      (node (ref "C1") (pin "2") (pinfunction "2_2") (pintype "passive"))
      (node (ref "C11") (pin "1") (pinfunction "1_1") (pintype "passive"))
      (node (ref "C12") (pin "1") (pinfunction "1_1") (pintype "passive"))
      (node (ref "C14") (pin "2") (pinfunction "2_2") (pintype "passive"))
      (node (ref "C15") (pin "2") (pinfunction "2_2") (pintype "passive"))
      (node (ref "C16") (pin "1") (pinfunction "1_1") (pintype "passive"))
      (node (ref "C2") (pin "2") (pinfunction "2_2") (pintype "passive"))
      (node (ref "C24") (pin "1") (pinfunction "1_1") (pintype "passive"))
      (node (ref "C25") (pin "1") (pinfunction "1_1") (pintype "passive"))
      (node (ref "C26") (pin "2") (pinfunction "2_2") (pintype "passive"))
      (node (ref "C27") (pin "2") (pinfunction "2_2") (pintype "passive"))
      (node (ref "C28") (pin "1") (pinfunction "1_1") (pintype "passive"))
      (node (ref "C29") (pin "2") (pinfunction "2_2") (pintype "passive"))
      (node (ref "C3") (pin "2") (pinfunction "2_2") (pintype "passive"))
      (node (ref "C30") (pin "1") (pinfunction "1_1") (pintype "passive"))
      (node (ref "C31") (pin "1") (pinfunction "1_1") (pintype "passive"))
      (node (ref "C32") (pin "2") (pinfunction "2_2") (pintype "passive"))
      (node (ref "C37") (pin "2") (pinfunction "2_2") (pintype "passive"))
      (node (ref "C38") (pin "1") (pinfunction "1_1") (pintype "passive"))
      (node (ref "C39") (pin "1") (pinfunction "1_1") (pintype "passive"))
      (node (ref "C4") (pin "1") (pinfunction "1_1") (pintype "passive"))
      (node (ref "C5") (pin "2") (pinfunction "2_2") (pintype "passive"))
      (node (ref "C6") (pin "2") (pinfunction "2_2") (pintype "passive"))
      (node (ref "C7") (pin "1") (pinfunction "1_1") (pintype "passive"))
      (node (ref "D1") (pin "1") (pinfunction "A_1") (pintype "passive"))
      (node (ref "D3") (pin "2") (pintype "passive"))
      (node (ref "P1") (pin "2") (pinfunction "2_2") (pintype "passive"))
      (node (ref "P3") (pin "2") (pinfunction "2_2") (pintype "passive"))
      (node (ref "R1") (pin "2") (pinfunction "2_2") (pintype "passive"))
      (node (ref "R11") (pin "2") (pinfunction "2_2") (pintype "passive"))
      (node (ref "R15") (pin "2") (pinfunction "2_2") (pintype "passive"))
      (node (ref "R22") (pin "2") (pinfunction "0_2") (pintype "passive"))
      (node (ref "R29") (pin "1") (pinfunction "0_1") (pintype "passive"))
      (node (ref "R36") (pin "1") (pinfunction "0_1") (pintype "passive"))
      (node (ref "R37") (pin "2") (pinfunction "0_2") (pintype "passive"))
      (node (ref "R38") (pin "1") (pinfunction "1_1") (pintype "passive"))
      (node (ref "R39") (pin "2") (pinfunction "0_2") (pintype "passive"))
      (node (ref "R6") (pin "2") (pinfunction "2_2") (pintype "passive"))
      (node (ref "U1") (pin "2") (pinfunction "GND_2") (pintype "passive"))
      (node (ref "U1") (pin "9") (pinfunction "EP_9") (pintype "passive"))
      (node (ref "U2") (pin "49") (pinfunction "EPAD_49") (pintype "passive"))
      (node (ref "U3") (pin "2") (pinfunction "GND_2") (pintype "passive"))
      (node (ref "U4") (pin "2") (pinfunction "GND_2") (pintype "passive"))
      (node (ref "U5") (pin "32") (pinfunction "AGND_32") (pintype "passive"))
      (node (ref "U6") (pin "13") (pinfunction "GND_13") (pintype "passive"))
      (node (ref "U6") (pin "5") (pinfunction "TEST_5") (pintype "passive"))
      (node (ref "U7") (pin "13") (pinfunction "GND_13") (pintype "passive"))
      (node (ref "U7") (pin "5") (pinfunction "TEST_5") (pintype "passive"))
    )
    (net (code "58") (name "M1_GND") (class "Default")
      (node (ref "R29") (pin "2") (pinfunction "0_2") (pintype "passive"))
    )
    (net (code "59") (name "Net-(C17-Pad2)") (class "Default")
      (node (ref "C17") (pin "2") (pinfunction "2_2") (pintype "passive"))
      (node (ref "NT1") (pin "2") (pintype "passive"))
      (node (ref "Q2") (pin "1") (pinfunction "S_1") (pintype "passive"))
      (node (ref "Q2") (pin "2") (pinfunction "S_2") (pintype "passive"))
      (node (ref "Q2") (pin "3") (pinfunction "S_3") (pintype "passive"))
      (node (ref "R28") (pin "2") (pinfunction "0_2") (pintype "passive"))
    )
    (net (code "60") (name "Net-(C18-Pad2)") (class "Default")
      (node (ref "C18") (pin "2") (pinfunction "2_2") (pintype "passive"))
      (node (ref "NT3") (pin "2") (pintype "passive"))
      (node (ref "Q4") (pin "1") (pinfunction "S_1") (pintype "passive"))
      (node (ref "Q4") (pin "2") (pinfunction "S_2") (pintype "passive"))
      (node (ref "Q4") (pin "3") (pinfunction "S_3") (pintype "passive"))
      (node (ref "R18") (pin "2") (pinfunction "0_2") (pintype "passive"))
    )
    (net (code "61") (name "Net-(C19-Pad2)") (class "Default")
      (node (ref "C19") (pin "2") (pinfunction "2_2") (pintype "passive"))
      (node (ref "NT5") (pin "2") (pintype "passive"))
      (node (ref "Q6") (pin "1") (pinfunction "S_1") (pintype "passive"))
      (node (ref "Q6") (pin "2") (pinfunction "S_2") (pintype "passive"))
      (node (ref "Q6") (pin "3") (pinfunction "S_3") (pintype "passive"))
      (node (ref "R19") (pin "2") (pinfunction "0_2") (pintype "passive"))
    )
    (net (code "62") (name "Net-(CN1-Pad4)") (class "Default")
      (node (ref "CN1") (pin "4") (pinfunction "4_4") (pintype "passive"))
      (node (ref "CN1") (pin "5") (pinfunction "5_5") (pintype "passive"))
    )
    (net (code "63") (name "Net-(CN2-Pad4)") (class "Default")
      (node (ref "CN2") (pin "4") (pinfunction "4_4") (pintype "passive"))
      (node (ref "CN2") (pin "5") (pinfunction "5_5") (pintype "passive"))
    )
    (net (code "64") (name "Net-(D1-K)") (class "Default")
      (node (ref "C10") (pin "1") (pinfunction "1_1") (pintype "passive"))
      (node (ref "C8") (pin "1") (pinfunction "1_1") (pintype "passive"))
      (node (ref "D1") (pin "2") (pinfunction "K_2") (pintype "passive"))
      (node (ref "L1") (pin "1") (pintype "passive"))
      (node (ref "U4") (pin "6") (pinfunction "SW_6") (pintype "passive"))
    )
    (net (code "65") (name "Net-(D2-K)") (class "Default")
      (node (ref "C13") (pin "1") (pinfunction "1_1") (pintype "passive"))
      (node (ref "D2") (pin "2") (pinfunction "K_2") (pintype "passive"))
      (node (ref "R10") (pin "2") (pinfunction "2_2") (pintype "passive"))
      (node (ref "U4") (pin "5") (pinfunction "IN_5") (pintype "passive"))
    )
    (net (code "66") (name "Net-(D3-Pad1)") (class "Default")
      (node (ref "D3") (pin "1") (pintype "passive"))
      (node (ref "P3") (pin "1") (pinfunction "1_1") (pintype "passive"))
      (node (ref "R13") (pin "2") (pinfunction "2_2") (pintype "passive"))
    )
    (net (code "67") (name "Net-(LED1-ANODE)") (class "Default")
      (node (ref "LED1") (pin "A") (pinfunction "ANODE_A") (pintype "passive"))
      (node (ref "R7") (pin "2") (pinfunction "2_2") (pintype "passive"))
    )
    (net (code "68") (name "Net-(LED2-ANODE)") (class "Default")
      (node (ref "LED2") (pin "A") (pinfunction "ANODE_A") (pintype "passive"))
      (node (ref "R9") (pin "2") (pinfunction "2_2") (pintype "passive"))
    )
    (net (code "69") (name "Net-(U2A-PB10)") (class "Default")
      (node (ref "R15") (pin "1") (pinfunction "1_1") (pintype "passive"))
      (node (ref "U2") (pin "22") (pinfunction "PB10_22") (pintype "passive"))
    )
    (net (code "70") (name "Net-(U2A-PB14)") (class "Default")
      (node (ref "C37") (pin "1") (pinfunction "1_1") (pintype "passive"))
      (node (ref "R12") (pin "2") (pinfunction "2_2") (pintype "passive"))
      (node (ref "R13") (pin "1") (pinfunction "1_1") (pintype "passive"))
      (node (ref "U2") (pin "27") (pinfunction "PB14_27") (pintype "passive"))
    )
    (net (code "71") (name "Net-(U2A-PF0-OSC_IN)") (class "Default")
      (node (ref "R2") (pin "2") (pinfunction "0_2") (pintype "passive"))
      (node (ref "U2") (pin "5") (pinfunction "PF0-OSC_IN_5") (pintype "passive"))
    )
    (net (code "72") (name "Net-(U4-BS)") (class "Default")
      (node (ref "C10") (pin "2") (pinfunction "2_2") (pintype "passive"))
      (node (ref "C8") (pin "2") (pinfunction "2_2") (pintype "passive"))
      (node (ref "U4") (pin "1") (pinfunction "BS_1") (pintype "passive"))
    )
    (net (code "73") (name "Net-(U4-EN)") (class "Default")
      (node (ref "R10") (pin "1") (pinfunction "1_1") (pintype "passive"))
      (node (ref "U4") (pin "4") (pinfunction "EN_4") (pintype "passive"))
    )
    (net (code "74") (name "Net-(U4-FB)") (class "Default")
      (node (ref "C9") (pin "2") (pinfunction "2_2") (pintype "passive"))
      (node (ref "R4") (pin "2") (pinfunction "2_2") (pintype "passive"))
      (node (ref "R6") (pin "1") (pinfunction "1_1") (pintype "passive"))
      (node (ref "U4") (pin "3") (pinfunction "FB_3") (pintype "passive"))
    )
    (net (code "75") (name "Net-(U5-CPH)") (class "Default")
      (node (ref "C20") (pin "1") (pinfunction "1_1") (pintype "passive"))
      (node (ref "U5") (pin "2") (pinfunction "CPH_2") (pintype "passive"))
    )
    (net (code "76") (name "Net-(U5-CPL)") (class "Default")
      (node (ref "C20") (pin "2") (pinfunction "2_2") (pintype "passive"))
      (node (ref "U5") (pin "1") (pinfunction "CPL_1") (pintype "passive"))
    )
    (net (code "77") (name "Net-(U5-DVDD)") (class "Default")
      (node (ref "C24") (pin "2") (pinfunction "2_2") (pintype "passive"))
      (node (ref "U5") (pin "33") (pinfunction "DVDD_33") (pintype "passive"))
    )
    (net (code "78") (name "Net-(U5-SOA)") (class "Default")
      (node (ref "R32") (pin "2") (pinfunction "2_2") (pintype "passive"))
      (node (ref "U5") (pin "23") (pinfunction "SOA_23") (pintype "passive"))
    )
    (net (code "79") (name "Net-(U5-SOB)") (class "Default")
      (node (ref "R35") (pin "2") (pinfunction "2_2") (pintype "passive"))
      (node (ref "U5") (pin "22") (pinfunction "SOB_22") (pintype "passive"))
    )
    (net (code "80") (name "Net-(U5-SOC)") (class "Default")
      (node (ref "R40") (pin "2") (pinfunction "2_2") (pintype "passive"))
      (node (ref "U5") (pin "21") (pinfunction "SOC_21") (pintype "passive"))
    )
    (net (code "81") (name "Net-(U5-VCP)") (class "Default")
      (node (ref "C21") (pin "1") (pinfunction "1_1") (pintype "passive"))
      (node (ref "U5") (pin "3") (pinfunction "VCP_3") (pintype "passive"))
    )
    (net (code "82") (name "Net-(U6-VDD)") (class "Default")
      (node (ref "R41") (pin "2") (pinfunction "0_2") (pintype "passive"))
      (node (ref "U6") (pin "11") (pinfunction "VDD_11") (pintype "passive"))
    )
    (net (code "83") (name "Net-(U7-VDD)") (class "Default")
      (node (ref "R3") (pin "2") (pinfunction "0_2") (pintype "passive"))
      (node (ref "U7") (pin "11") (pinfunction "VDD_11") (pintype "passive"))
    )
    (net (code "84") (name "PGND") (class "Default")
      (node (ref "C13") (pin "2") (pinfunction "2_2") (pintype "passive"))
      (node (ref "C22") (pin "2") (pinfunction "2_2") (pintype "passive"))
      (node (ref "C23") (pin "2") (pinfunction "2_2") (pintype "passive"))
      (node (ref "C33") (pin "1") (pinfunction "1_1") (pintype "passive"))
      (node (ref "C34") (pin "1") (pinfunction "1_1") (pintype "passive"))
      (node (ref "C35") (pin "1") (pinfunction "1_1") (pintype "passive"))
      (node (ref "C36") (pin "1") (pinfunction "1_1") (pintype "passive"))
      (node (ref "D6") (pin "2") (pintype "passive"))
      (node (ref "D7") (pin "2") (pintype "passive"))
      (node (ref "D8") (pin "2") (pintype "passive"))
      (node (ref "NT2") (pin "2") (pintype "passive"))
      (node (ref "NT4") (pin "2") (pintype "passive"))
      (node (ref "NT6") (pin "2") (pintype "passive"))
      (node (ref "P5") (pin "1") (pinfunction "1_1") (pintype "passive"))
      (node (ref "P6") (pin "1") (pinfunction "1_1") (pintype "passive"))
      (node (ref "R18") (pin "1") (pinfunction "0_1") (pintype "passive"))
      (node (ref "R19") (pin "1") (pinfunction "0_1") (pintype "passive"))
      (node (ref "R22") (pin "1") (pinfunction "0_1") (pintype "passive"))
      (node (ref "R28") (pin "1") (pinfunction "0_1") (pintype "passive"))
      (node (ref "U5") (pin "40") (pinfunction "PGND_40") (pintype "passive"))
      (node (ref "U5") (pin "41") (pinfunction "EP_41") (pintype "passive"))
    )
    (net (code "85") (name "VCC") (class "Default")
      (node (ref "C14") (pin "1") (pinfunction "1_1") (pintype "passive"))
      (node (ref "C15") (pin "1") (pinfunction "1_1") (pintype "passive"))
      (node (ref "C2") (pin "1") (pinfunction "1_1") (pintype "passive"))
      (node (ref "C25") (pin "2") (pinfunction "2_2") (pintype "passive"))
      (node (ref "C3") (pin "1") (pinfunction "1_1") (pintype "passive"))
      (node (ref "C32") (pin "1") (pinfunction "1_1") (pintype "passive"))
      (node (ref "C38") (pin "2") (pinfunction "2_2") (pintype "passive"))
      (node (ref "C39") (pin "2") (pinfunction "2_2") (pintype "passive"))
      (node (ref "C4") (pin "2") (pinfunction "2_2") (pintype "passive"))
      (node (ref "C5") (pin "1") (pinfunction "1_1") (pintype "passive"))
      (node (ref "C6") (pin "1") (pinfunction "1_1") (pintype "passive"))
      (node (ref "C7") (pin "2") (pinfunction "2_2") (pintype "passive"))
      (node (ref "P2") (pin "1") (pinfunction "1_1") (pintype "passive"))
      (node (ref "R12") (pin "1") (pinfunction "1_1") (pintype "passive"))
      (node (ref "R3") (pin "1") (pinfunction "0_1") (pintype "passive"))
      (node (ref "R30") (pin "2") (pinfunction "2_2") (pintype "passive"))
      (node (ref "R31") (pin "2") (pinfunction "2_2") (pintype "passive"))
      (node (ref "R34") (pin "2") (pinfunction "0_2") (pintype "passive"))
      (node (ref "R41") (pin "1") (pinfunction "0_1") (pintype "passive"))
      (node (ref "R5") (pin "1") (pinfunction "1_1") (pintype "passive"))
      (node (ref "R7") (pin "1") (pinfunction "1_1") (pintype "passive"))
      (node (ref "R8") (pin "1") (pinfunction "1_1") (pintype "passive"))
      (node (ref "R9") (pin "1") (pinfunction "1_1") (pintype "passive"))
      (node (ref "U1") (pin "5") (pinfunction "VIO_5") (pintype "passive"))
      (node (ref "U2") (pin "1") (pinfunction "VBAT_1") (pintype "passive"))
      (node (ref "U2") (pin "20") (pinfunction "VREF+_20") (pintype "passive"))
      (node (ref "U2") (pin "21") (pinfunction "VDDA_21") (pintype "passive"))
      (node (ref "U2") (pin "23") (pinfunction "VDD_23") (pintype "passive"))
      (node (ref "U2") (pin "35") (pinfunction "VDD_35") (pintype "passive"))
      (node (ref "U2") (pin "48") (pinfunction "VDD_48") (pintype "passive"))
      (node (ref "U3") (pin "5") (pinfunction "VOUT_5") (pintype "passive"))
      (node (ref "U5") (pin "24") (pinfunction "VREF_24") (pintype "passive"))
      (node (ref "U6") (pin "12") (pinfunction "VDD3V_12") (pintype "passive"))
      (node (ref "U7") (pin "12") (pinfunction "VDD3V_12") (pintype "passive"))
    )
    (net (code "86") (name "VCC_5V") (class "Default")
      (node (ref "C1") (pin "1") (pinfunction "1_1") (pintype "passive"))
      (node (ref "C11") (pin "2") (pinfunction "2_2") (pintype "passive"))
      (node (ref "C12") (pin "2") (pinfunction "2_2") (pintype "passive"))
      (node (ref "C9") (pin "1") (pinfunction "1_1") (pintype "passive"))
      (node (ref "L1") (pin "2") (pinfunction "2_2") (pintype "passive"))
      (node (ref "R4") (pin "1") (pinfunction "1_1") (pintype "passive"))
      (node (ref "U1") (pin "3") (pinfunction "VCC_3") (pintype "passive"))
      (node (ref "U3") (pin "1") (pinfunction "VIN_1") (pintype "passive"))
      (node (ref "U3") (pin "3") (pinfunction "ON/OFF_3") (pintype "passive"))
    )
    (net (code "87") (name "unconnected-(U2A-PB11-Pad24)") (class "Default")
      (node (ref "U2") (pin "24") (pinfunction "PB11_24") (pintype "passive"))
    )
    (net (code "88") (name "unconnected-(U2A-PC4-Pad16)") (class "Default")
      (node (ref "U2") (pin "16") (pinfunction "PC4_16") (pintype "passive"))
    )
    (net (code "89") (name "unconnected-(U3-BYPASS-Pad4)") (class "Default")
      (node (ref "U3") (pin "4") (pinfunction "BYPASS_4") (pintype "passive"))
    )
    (net (code "90") (name "unconnected-(U5-CAL-Pad31)") (class "Default")
      (node (ref "U5") (pin "31") (pinfunction "CAL_31") (pintype "passive"))
    )
    (net (code "91") (name "unconnected-(U6-A-Pad7)") (class "Default")
      (node (ref "U6") (pin "7") (pinfunction "A_7") (pintype "passive"))
    )
    (net (code "92") (name "unconnected-(U6-B-Pad6)") (class "Default")
      (node (ref "U6") (pin "6") (pinfunction "B_6") (pintype "passive"))
    )
    (net (code "93") (name "unconnected-(U6-I{slash}PWM-Pad14)") (class "Default")
      (node (ref "U6") (pin "14") (pinfunction "I/PWM_14") (pintype "passive"))
    )
    (net (code "94") (name "unconnected-(U6-U-Pad10)") (class "Default")
      (node (ref "U6") (pin "10") (pinfunction "U_10") (pintype "passive"))
    )
    (net (code "95") (name "unconnected-(U6-V-Pad9)") (class "Default")
      (node (ref "U6") (pin "9") (pinfunction "V_9") (pintype "passive"))
    )
    (net (code "96") (name "unconnected-(U6-W{slash}PWM-Pad8)") (class "Default")
      (node (ref "U6") (pin "8") (pinfunction "W/PWM_8") (pintype "passive"))
    )
    (net (code "97") (name "unconnected-(U7-A-Pad7)") (class "Default")
      (node (ref "U7") (pin "7") (pinfunction "A_7") (pintype "passive"))
    )
    (net (code "98") (name "unconnected-(U7-B-Pad6)") (class "Default")
      (node (ref "U7") (pin "6") (pinfunction "B_6") (pintype "passive"))
    )
    (net (code "99") (name "unconnected-(U7-I{slash}PWM-Pad14)") (class "Default")
      (node (ref "U7") (pin "14") (pinfunction "I/PWM_14") (pintype "passive"))
    )
    (net (code "100") (name "unconnected-(U7-U-Pad10)") (class "Default")
      (node (ref "U7") (pin "10") (pinfunction "U_10") (pintype "passive"))
    )
    (net (code "101") (name "unconnected-(U7-V-Pad9)") (class "Default")
      (node (ref "U7") (pin "9") (pinfunction "V_9") (pintype "passive"))
    )
    (net (code "102") (name "unconnected-(U7-W{slash}PWM-Pad8)") (class "Default")
      (node (ref "U7") (pin "8") (pinfunction "W/PWM_8") (pintype "passive"))
    )
  )
)
